# dasblinkenhat-controller-mk-3_1.net
KiCad netlist of a schematic drawn in EAGLE
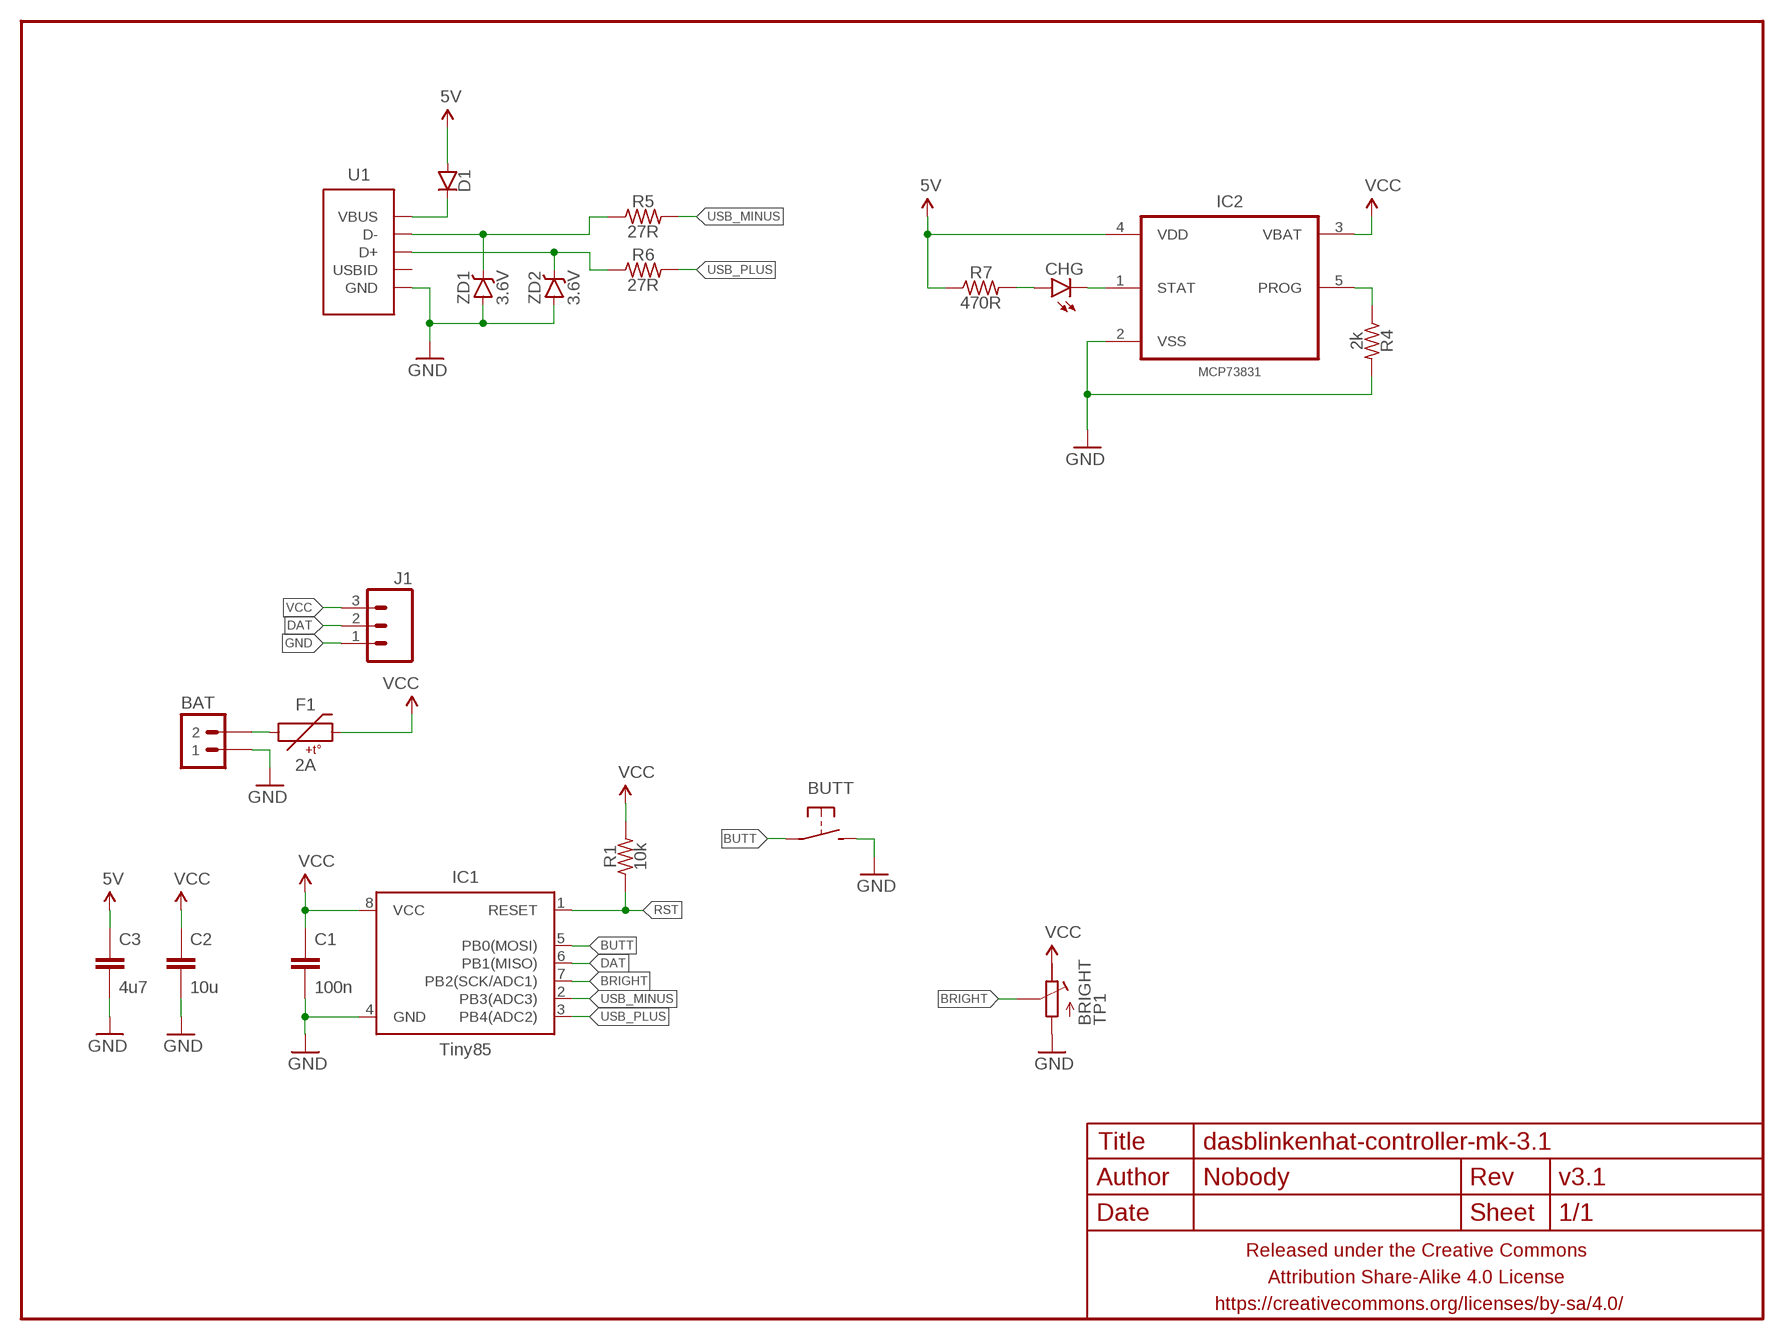
[diagram p0: schematic, sheet 1]

(export (version "E")
  (design (tool "Eeschema 10.0.6"))
  (components
    (comp (ref "BAT")
      (value "M02JST-2MM-SMT")
      (footprint "eagle-import:JST-2-SMD")
      (libsource (lib "eagle-import") (part "M02JST-2MM-SMT"))
    )
    (comp (ref "BUTT")
      (value "DTS-6MM")
      (footprint "eagle-import:DTSM-6")
      (libsource (lib "eagle-import") (part "SPST-NO-TACT6MM-SMD"))
    )
    (comp (ref "C1")
      (value "100n")
      (footprint "eagle-import:C0603")
      (libsource (lib "eagle-import") (part "CAPACITOR-CERAMICC0603"))
    )
    (comp (ref "C2")
      (value "10u")
      (footprint "eagle-import:C0805")
      (libsource (lib "eagle-import") (part "CAPACITOR-CERAMICC0805"))
    )
    (comp (ref "C3")
      (value "4u7")
      (footprint "eagle-import:C0805")
      (libsource (lib "eagle-import") (part "a_parts_CAPACITOR-CERAMICC0805"))
    )
    (comp (ref "CHG")
      (value "LED0603")
      (footprint "eagle-import:LED-0603")
      (libsource (lib "eagle-import") (part "LED0603"))
    )
    (comp (ref "D1")
      (value "DIODESOD123")
      (footprint "eagle-import:SOD123")
      (libsource (lib "eagle-import") (part "DIODESOD123"))
    )
    (comp (ref "F1")
      (value "2A")
      (footprint "eagle-import:PTC-1206")
      (libsource (lib "eagle-import") (part "PTCSMD"))
    )
    (comp (ref "FRAME1")
      (value "FRAME-LETTERNO_PACKAGE")
      (footprint "eagle-import:DUMMY")
      (fields (field (name "VERSION") "v3.1") (field (name "DESIGNER") "Nobody"))
      (libsource (lib "eagle-import") (part "FRAME-LETTERNO_PACKAGE"))
    )
    (comp (ref "IC1")
      (value "Tiny85")
      (footprint "eagle-import:SO08-EIAJ")
      (libsource (lib "eagle-import") (part "ATTINY45TINY85-20-SOICW"))
    )
    (comp (ref "IC2")
      (value "MCP73831")
      (footprint "eagle-import:SOT95P280X145-5N")
      (fields (field (name "MPN") "MCP73831T-2ACI/OT"))
      (libsource (lib "eagle-import") (part "MCP73831T-2ACI/OT"))
    )
    (comp (ref "J1")
      (value "M03JST-XH-RA-PTH")
      (footprint "eagle-import:JST-3-XH-RA-PTH")
      (libsource (lib "eagle-import") (part "M03JST-XH-RA-PTH"))
    )
    (comp (ref "R1")
      (value "10k")
      (footprint "eagle-import:R0603")
      (libsource (lib "eagle-import") (part "RESISTORR0603"))
    )
    (comp (ref "R4")
      (value "2k")
      (footprint "eagle-import:R0603")
      (libsource (lib "eagle-import") (part "RESISTORR0603"))
    )
    (comp (ref "R5")
      (value "27R")
      (footprint "eagle-import:R0603")
      (libsource (lib "eagle-import") (part "RESISTORR0603"))
    )
    (comp (ref "R6")
      (value "27R")
      (footprint "eagle-import:R0603")
      (libsource (lib "eagle-import") (part "RESISTORR0603"))
    )
    (comp (ref "R7")
      (value "470R")
      (footprint "eagle-import:R0603")
      (libsource (lib "eagle-import") (part "RESISTORR0603"))
    )
    (comp (ref "TP1")
      (value "BRIGHT")
      (footprint "eagle-import:EVM3Y")
      (libsource (lib "eagle-import") (part "POTENTIOMETEREVM3Y"))
    )
    (comp (ref "U1")
      (value "USB-ABFCI-10103594-USB-MICRO-B-LESS")
      (footprint "eagle-import:FCI-10103594-USB-MICRO-B-LESS")
      (libsource (lib "eagle-import") (part "USB-ABFCI-10103594-USB-MICRO-B-LESS"))
    )
    (comp (ref "ZD1")
      (value "3.6V")
      (footprint "eagle-import:SOD323-ZENNER")
      (libsource (lib "eagle-import") (part "DIODE-ZENERSOD323"))
    )
    (comp (ref "ZD2")
      (value "3.6V")
      (footprint "eagle-import:SOD323-ZENNER")
      (libsource (lib "eagle-import") (part "DIODE-ZENERSOD323"))
    )
  )
  (nets
    (net (code "1") (name "5V") (class "Default")
      (node (ref "C3") (pin "1") (pinfunction "1_1") (pintype "passive"))
      (node (ref "D1") (pin "A") (pinfunction "A_A") (pintype "passive"))
      (node (ref "IC2") (pin "4") (pinfunction "VDD_4") (pintype "power_in"))
      (node (ref "R7") (pin "1") (pinfunction "1_1") (pintype "passive"))
    )
    (net (code "2") (name "BRIGHT") (class "Default")
      (node (ref "IC1") (pin "7") (pinfunction "PB2(SCK/ADC1)_7") (pintype "bidirectional"))
      (node (ref "TP1") (pin "S") (pinfunction "S_S") (pintype "passive"))
    )
    (net (code "3") (name "BUTT") (class "Default")
      (node (ref "BUTT") (pin "1") (pinfunction "1_1") (pintype "passive"))
      (node (ref "BUTT") (pin "2") (pinfunction "1_2") (pintype "passive"))
      (node (ref "IC1") (pin "5") (pinfunction "PB0(MOSI)_5") (pintype "bidirectional"))
    )
    (net (code "4") (name "DAT") (class "Default")
      (node (ref "IC1") (pin "6") (pinfunction "PB1(MISO)_6") (pintype "bidirectional"))
      (node (ref "J1") (pin "2") (pinfunction "2_2") (pintype "passive"))
    )
    (net (code "5") (name "GND") (class "Default")
      (node (ref "BAT") (pin "2") (pinfunction "1_2") (pintype "passive"))
      (node (ref "BUTT") (pin "3") (pinfunction "2_3") (pintype "passive"))
      (node (ref "BUTT") (pin "4") (pinfunction "2_4") (pintype "passive"))
      (node (ref "C1") (pin "2") (pinfunction "2_2") (pintype "passive"))
      (node (ref "C2") (pin "2") (pinfunction "2_2") (pintype "passive"))
      (node (ref "C3") (pin "2") (pinfunction "2_2") (pintype "passive"))
      (node (ref "IC1") (pin "4") (pinfunction "GND_4") (pintype "bidirectional"))
      (node (ref "IC2") (pin "2") (pinfunction "VSS_2") (pintype "power_in"))
      (node (ref "J1") (pin "1") (pinfunction "1_1") (pintype "passive"))
      (node (ref "R4") (pin "2") (pinfunction "2_2") (pintype "passive"))
      (node (ref "TP1") (pin "A") (pinfunction "A_A") (pintype "passive"))
      (node (ref "U1") (pin "5") (pinfunction "GND_5") (pintype "bidirectional"))
      (node (ref "ZD1") (pin "A") (pinfunction "A_A") (pintype "passive"))
      (node (ref "ZD2") (pin "A") (pinfunction "A_A") (pintype "passive"))
    )
    (net (code "6") (name "Net-(BAT-2)") (class "Default")
      (node (ref "BAT") (pin "1") (pinfunction "2_1") (pintype "passive"))
      (node (ref "F1") (pin "1") (pinfunction "1_1") (pintype "passive"))
    )
    (net (code "7") (name "Net-(CHG-PadA)") (class "Default")
      (node (ref "CHG") (pin "A") (pinfunction "A_A") (pintype "passive"))
      (node (ref "R7") (pin "2") (pinfunction "2_2") (pintype "passive"))
    )
    (net (code "8") (name "Net-(IC2-PROG)") (class "Default")
      (node (ref "IC2") (pin "5") (pinfunction "PROG_5") (pintype "input"))
      (node (ref "R4") (pin "1") (pinfunction "1_1") (pintype "passive"))
    )
    (net (code "9") (name "Net-(IC2-STAT)") (class "Default")
      (node (ref "CHG") (pin "C") (pinfunction "C_C") (pintype "passive"))
      (node (ref "IC2") (pin "1") (pinfunction "STAT_1") (pintype "output"))
    )
    (net (code "10") (name "Net-(U1-D+)") (class "Default")
      (node (ref "R6") (pin "1") (pinfunction "1_1") (pintype "passive"))
      (node (ref "U1") (pin "3") (pinfunction "D+_3") (pintype "bidirectional"))
      (node (ref "ZD2") (pin "C") (pinfunction "C_C") (pintype "passive"))
    )
    (net (code "11") (name "Net-(U1-D-)") (class "Default")
      (node (ref "R5") (pin "1") (pinfunction "1_1") (pintype "passive"))
      (node (ref "U1") (pin "2") (pinfunction "D-_2") (pintype "bidirectional"))
      (node (ref "ZD1") (pin "C") (pinfunction "C_C") (pintype "passive"))
    )
    (net (code "12") (name "Net-(U1-VBUS)") (class "Default")
      (node (ref "D1") (pin "C") (pinfunction "C_C") (pintype "passive"))
      (node (ref "U1") (pin "1") (pinfunction "VBUS_1") (pintype "bidirectional"))
    )
    (net (code "13") (name "RST") (class "Default")
      (node (ref "IC1") (pin "1") (pinfunction "RESET_1") (pintype "bidirectional"))
      (node (ref "R1") (pin "1") (pinfunction "1_1") (pintype "passive"))
    )
    (net (code "14") (name "USB_MINUS") (class "Default")
      (node (ref "IC1") (pin "2") (pinfunction "PB3(ADC3)_2") (pintype "bidirectional"))
      (node (ref "R5") (pin "2") (pinfunction "2_2") (pintype "passive"))
    )
    (net (code "15") (name "USB_PLUS") (class "Default")
      (node (ref "IC1") (pin "3") (pinfunction "PB4(ADC2)_3") (pintype "bidirectional"))
      (node (ref "R6") (pin "2") (pinfunction "2_2") (pintype "passive"))
    )
    (net (code "16") (name "VCC") (class "Default")
      (node (ref "C1") (pin "1") (pinfunction "1_1") (pintype "passive"))
      (node (ref "C2") (pin "1") (pinfunction "1_1") (pintype "passive"))
      (node (ref "F1") (pin "2") (pinfunction "2_2") (pintype "passive"))
      (node (ref "IC1") (pin "8") (pinfunction "VCC_8") (pintype "bidirectional"))
      (node (ref "IC2") (pin "3") (pinfunction "VBAT_3") (pintype "output"))
      (node (ref "J1") (pin "3") (pinfunction "3_3") (pintype "passive"))
      (node (ref "R1") (pin "2") (pinfunction "2_2") (pintype "passive"))
      (node (ref "TP1") (pin "E") (pinfunction "E_E") (pintype "passive"))
    )
    (net (code "17") (name "unconnected-(U1-USBID-Pad4)") (class "Default")
      (node (ref "U1") (pin "4") (pinfunction "USBID_4") (pintype "bidirectional"))
    )
  )
)
